# Arduino.net
KiCad netlist of a schematic drawn in Altium Designer
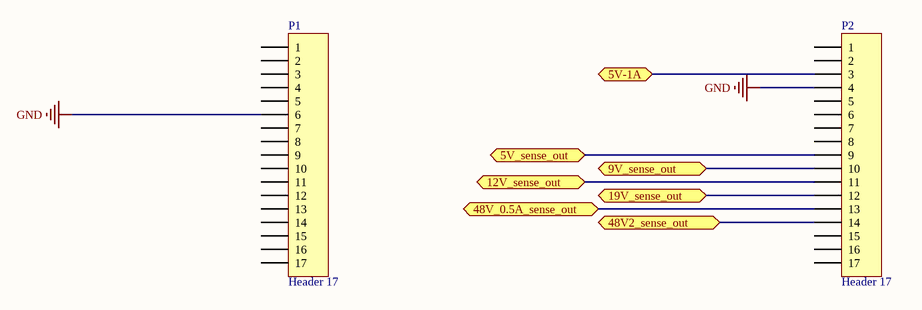
[diagram p0: Arduino.SchDoc]

(export (version "E")
  (design (tool "Eeschema 10.0.6"))
  (components
    (comp (ref "P1")
      (value "Header 17")
      (footprint "HDR1X17")
      (description "Header, 17-Pin")
      (fields (field (name "PUBLISHER") "Altium Limited"))
      (libsource (lib "Miscellaneous Connectors") (part "Header 17"))
    )
    (comp (ref "P2")
      (value "Header 17")
      (footprint "HDR1X17")
      (description "Header, 17-Pin")
      (fields (field (name "PUBLISHER") "Altium Limited"))
      (libsource (lib "Miscellaneous Connectors") (part "Header 17"))
    )
  )
  (nets
    (net (code "1") (name "/5V-1A") (class "Default")
      (node (ref "P2") (pin "3") (pinfunction "3_3") (pintype "passive"))
    )
    (net (code "2") (name "/5V_sense_out") (class "Default")
      (node (ref "P2") (pin "9") (pinfunction "9_9") (pintype "passive"))
    )
    (net (code "3") (name "/9V_sense_out") (class "Default")
      (node (ref "P2") (pin "10") (pinfunction "10_10") (pintype "passive"))
    )
    (net (code "4") (name "/12V_sense_out") (class "Default")
      (node (ref "P2") (pin "11") (pinfunction "11_11") (pintype "passive"))
    )
    (net (code "5") (name "/19V_sense_out") (class "Default")
      (node (ref "P2") (pin "12") (pinfunction "12_12") (pintype "passive"))
    )
    (net (code "6") (name "/48V2_sense_out") (class "Default")
      (node (ref "P2") (pin "14") (pinfunction "14_14") (pintype "passive"))
    )
    (net (code "7") (name "/48V_0.5A_sense_out") (class "Default")
      (node (ref "P2") (pin "13") (pinfunction "13_13") (pintype "passive"))
    )
    (net (code "8") (name "GND") (class "Default")
      (node (ref "P1") (pin "6") (pinfunction "6_6") (pintype "passive"))
      (node (ref "P2") (pin "4") (pinfunction "4_4") (pintype "passive"))
    )
    (net (code "9") (name "unconnected-(P1-Pad1)") (class "Default")
      (node (ref "P1") (pin "1") (pinfunction "1_1") (pintype "passive"))
    )
    (net (code "10") (name "unconnected-(P1-Pad2)") (class "Default")
      (node (ref "P1") (pin "2") (pinfunction "2_2") (pintype "passive"))
    )
    (net (code "11") (name "unconnected-(P1-Pad3)") (class "Default")
      (node (ref "P1") (pin "3") (pinfunction "3_3") (pintype "passive"))
    )
    (net (code "12") (name "unconnected-(P1-Pad4)") (class "Default")
      (node (ref "P1") (pin "4") (pinfunction "4_4") (pintype "passive"))
    )
    (net (code "13") (name "unconnected-(P1-Pad5)") (class "Default")
      (node (ref "P1") (pin "5") (pinfunction "5_5") (pintype "passive"))
    )
    (net (code "14") (name "unconnected-(P1-Pad7)") (class "Default")
      (node (ref "P1") (pin "7") (pinfunction "7_7") (pintype "passive"))
    )
    (net (code "15") (name "unconnected-(P1-Pad8)") (class "Default")
      (node (ref "P1") (pin "8") (pinfunction "8_8") (pintype "passive"))
    )
    (net (code "16") (name "unconnected-(P1-Pad9)") (class "Default")
      (node (ref "P1") (pin "9") (pinfunction "9_9") (pintype "passive"))
    )
    (net (code "17") (name "unconnected-(P1-Pad10)") (class "Default")
      (node (ref "P1") (pin "10") (pinfunction "10_10") (pintype "passive"))
    )
    (net (code "18") (name "unconnected-(P1-Pad11)") (class "Default")
      (node (ref "P1") (pin "11") (pinfunction "11_11") (pintype "passive"))
    )
    (net (code "19") (name "unconnected-(P1-Pad12)") (class "Default")
      (node (ref "P1") (pin "12") (pinfunction "12_12") (pintype "passive"))
    )
    (net (code "20") (name "unconnected-(P1-Pad13)") (class "Default")
      (node (ref "P1") (pin "13") (pinfunction "13_13") (pintype "passive"))
    )
    (net (code "21") (name "unconnected-(P1-Pad14)") (class "Default")
      (node (ref "P1") (pin "14") (pinfunction "14_14") (pintype "passive"))
    )
    (net (code "22") (name "unconnected-(P1-Pad15)") (class "Default")
      (node (ref "P1") (pin "15") (pinfunction "15_15") (pintype "passive"))
    )
    (net (code "23") (name "unconnected-(P1-Pad16)") (class "Default")
      (node (ref "P1") (pin "16") (pinfunction "16_16") (pintype "passive"))
    )
    (net (code "24") (name "unconnected-(P1-Pad17)") (class "Default")
      (node (ref "P1") (pin "17") (pinfunction "17_17") (pintype "passive"))
    )
    (net (code "25") (name "unconnected-(P2-Pad1)") (class "Default")
      (node (ref "P2") (pin "1") (pinfunction "1_1") (pintype "passive"))
    )
    (net (code "26") (name "unconnected-(P2-Pad2)") (class "Default")
      (node (ref "P2") (pin "2") (pinfunction "2_2") (pintype "passive"))
    )
    (net (code "27") (name "unconnected-(P2-Pad5)") (class "Default")
      (node (ref "P2") (pin "5") (pinfunction "5_5") (pintype "passive"))
    )
    (net (code "28") (name "unconnected-(P2-Pad6)") (class "Default")
      (node (ref "P2") (pin "6") (pinfunction "6_6") (pintype "passive"))
    )
    (net (code "29") (name "unconnected-(P2-Pad7)") (class "Default")
      (node (ref "P2") (pin "7") (pinfunction "7_7") (pintype "passive"))
    )
    (net (code "30") (name "unconnected-(P2-Pad8)") (class "Default")
      (node (ref "P2") (pin "8") (pinfunction "8_8") (pintype "passive"))
    )
    (net (code "31") (name "unconnected-(P2-Pad15)") (class "Default")
      (node (ref "P2") (pin "15") (pinfunction "15_15") (pintype "passive"))
    )
    (net (code "32") (name "unconnected-(P2-Pad16)") (class "Default")
      (node (ref "P2") (pin "16") (pinfunction "16_16") (pintype "passive"))
    )
    (net (code "33") (name "unconnected-(P2-Pad17)") (class "Default")
      (node (ref "P2") (pin "17") (pinfunction "17_17") (pintype "passive"))
    )
  )
)
